# Sensor_Node.net
KiCad netlist of a schematic drawn in EAGLE
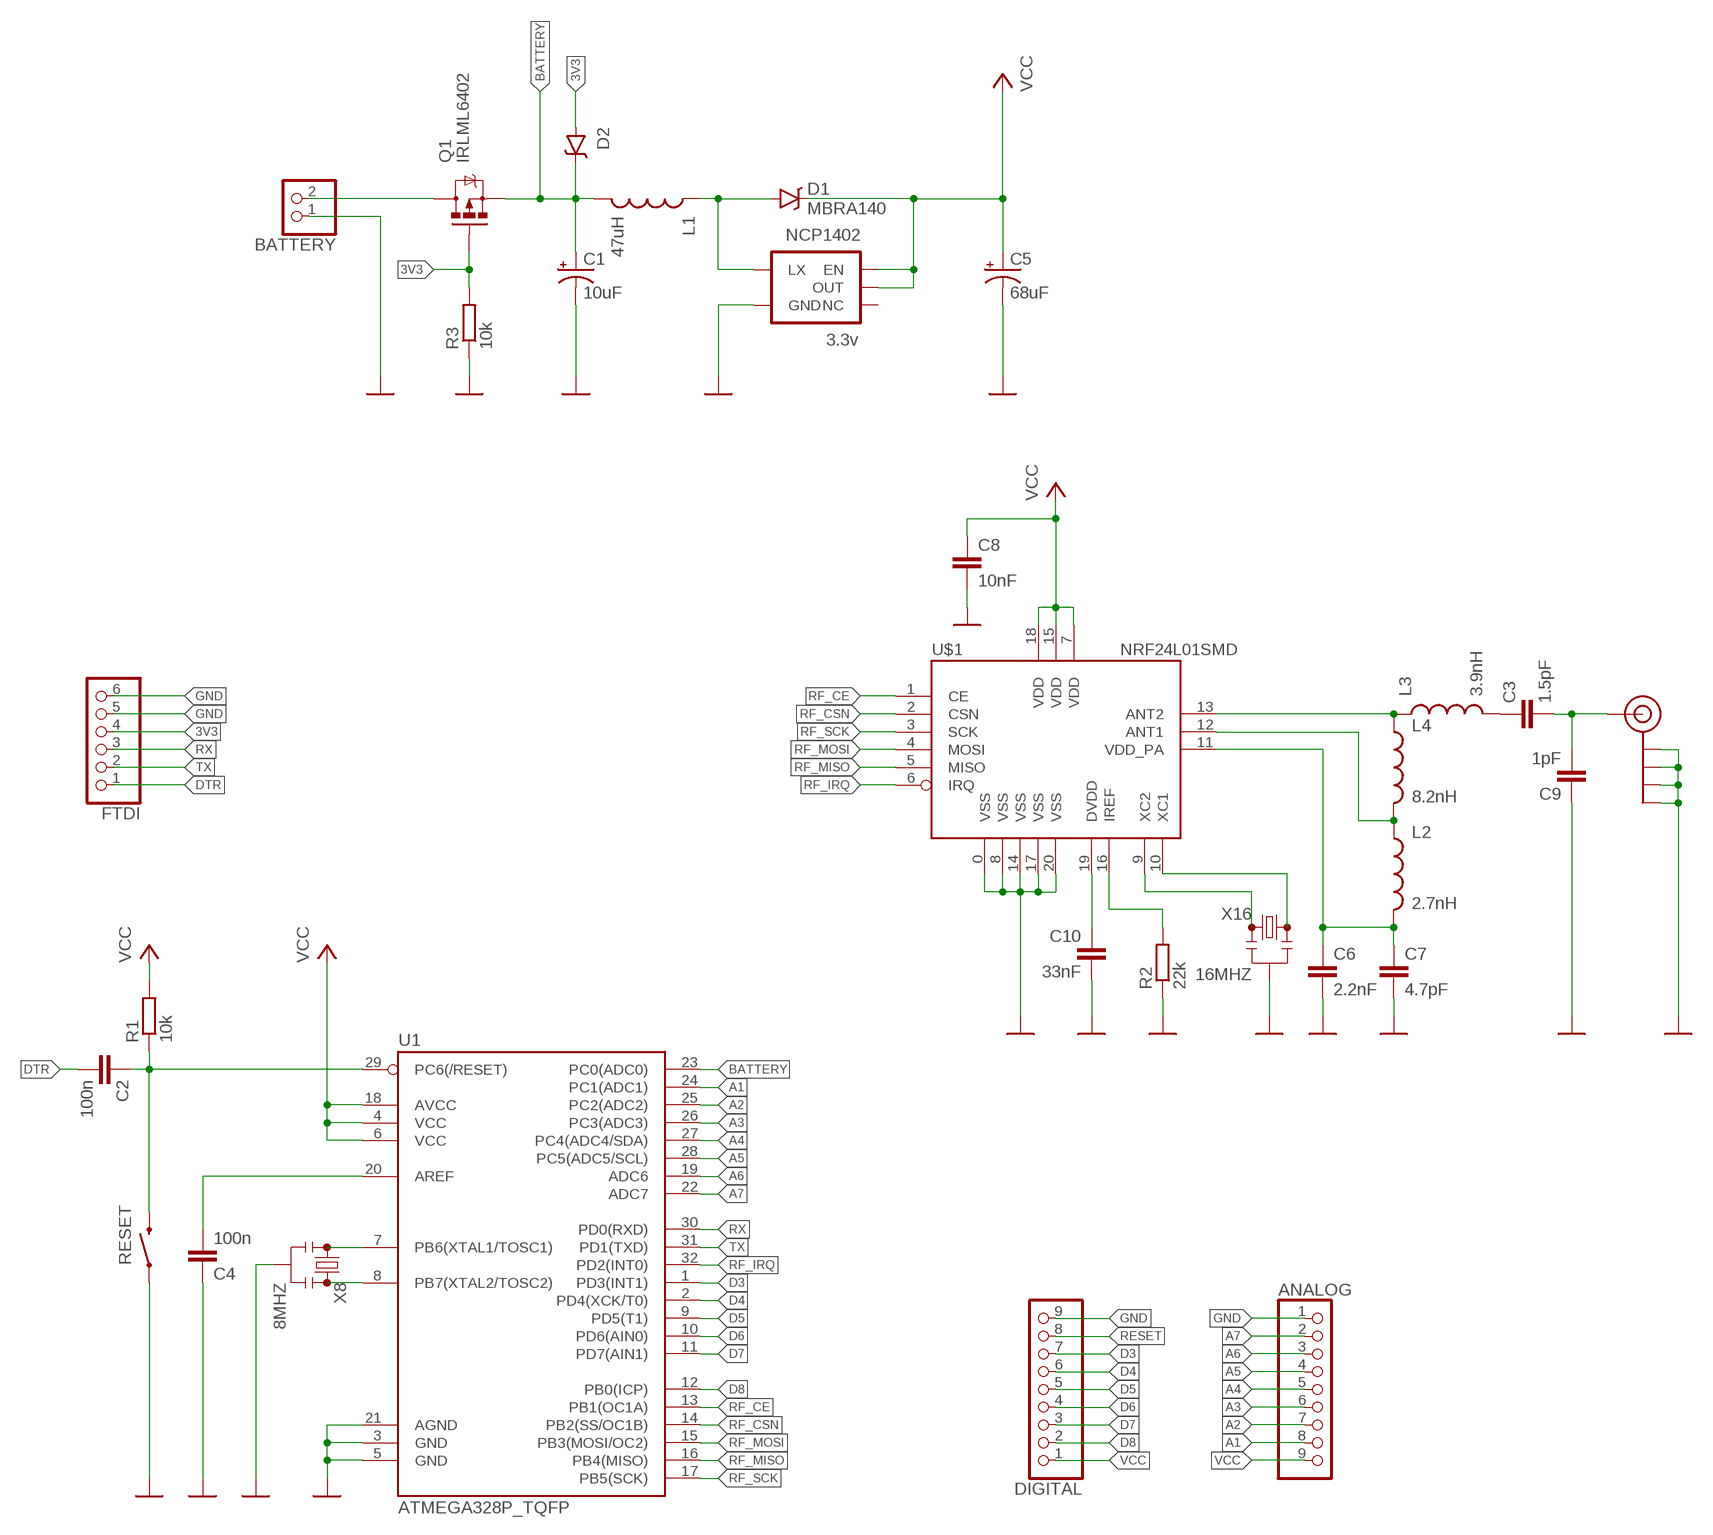
[diagram p0: schematic, sheet 1]

(export (version "E")
  (design (tool "Eeschema 10.0.6"))
  (components
    (comp (ref "ANALOG")
      (value "PINHD-1X9")
      (footprint "eagle-import:1X09")
      (libsource (lib "eagle-import") (part "PINHD-1X9"))
    )
    (comp (ref "BATTERY")
      (value "PINHD-1X2")
      (footprint "eagle-import:1X02")
      (libsource (lib "eagle-import") (part "PINHD-1X2"))
    )
    (comp (ref "C1")
      (value "10uF")
      (footprint "eagle-import:EIA3216-KIT")
      (libsource (lib "eagle-import") (part "CAP_POL1206-KIT"))
    )
    (comp (ref "C2")
      (value "100n")
      (footprint "eagle-import:C0402")
      (libsource (lib "eagle-import") (part "C-EUC0402"))
    )
    (comp (ref "C3")
      (value "1.5pF")
      (footprint "eagle-import:C0402")
      (libsource (lib "eagle-import") (part "C-EUC0402"))
    )
    (comp (ref "C4")
      (value "100n")
      (footprint "eagle-import:C0402")
      (libsource (lib "eagle-import") (part "C-EUC0402"))
    )
    (comp (ref "C5")
      (value "68uF")
      (footprint "eagle-import:EIA3528-KIT")
      (libsource (lib "eagle-import") (part "CAP_POL3528-KIT"))
    )
    (comp (ref "C6")
      (value "2.2nF")
      (footprint "eagle-import:C0402")
      (libsource (lib "eagle-import") (part "C-EUC0402"))
    )
    (comp (ref "C7")
      (value "4.7pF")
      (footprint "eagle-import:C0402")
      (libsource (lib "eagle-import") (part "C-EUC0402"))
    )
    (comp (ref "C8")
      (value "10nF")
      (footprint "eagle-import:C0402")
      (libsource (lib "eagle-import") (part "C-EUC0402"))
    )
    (comp (ref "C9")
      (value "1pF")
      (footprint "eagle-import:C0402")
      (libsource (lib "eagle-import") (part "C-EUC0402"))
    )
    (comp (ref "C10")
      (value "33nF")
      (footprint "eagle-import:C0402")
      (libsource (lib "eagle-import") (part "C-EUC0402"))
    )
    (comp (ref "D1")
      (value "MBRA140")
      (footprint "eagle-import:SMA-DIODE")
      (libsource (lib "eagle-import") (part "MBRA140"))
    )
    (comp (ref "D2")
      (value "MBRA140")
      (footprint "eagle-import:SMA-DIODE")
      (libsource (lib "eagle-import") (part "MBRA140"))
    )
    (comp (ref "DIGITAL")
      (value "PINHD-1X9")
      (footprint "eagle-import:1X09")
      (libsource (lib "eagle-import") (part "PINHD-1X9"))
    )
    (comp (ref "FTDI")
      (value "PINHD-1X6")
      (footprint "eagle-import:1X06")
      (libsource (lib "eagle-import") (part "PINHD-1X6"))
    )
    (comp (ref "J$1")
      (value "SMA_EDGE")
      (footprint "eagle-import:SMA-EDGE")
      (libsource (lib "eagle-import") (part "SMA_EDGE"))
    )
    (comp (ref "L1")
      (value "47uH")
      (footprint "eagle-import:CR54")
      (libsource (lib "eagle-import") (part "INDUCTORCR54-47UH"))
    )
    (comp (ref "L2")
      (value "2.7nH")
      (footprint "eagle-import:C0402")
      (libsource (lib "eagle-import") (part "INDUCTOR0402"))
    )
    (comp (ref "L3")
      (value "3.9nH")
      (footprint "eagle-import:C0402")
      (libsource (lib "eagle-import") (part "INDUCTOR0402"))
    )
    (comp (ref "L4")
      (value "8.2nH")
      (footprint "eagle-import:C0402")
      (libsource (lib "eagle-import") (part "INDUCTOR0402"))
    )
    (comp (ref "NCP1402")
      (value "3.3v")
      (footprint "eagle-import:SOT23-5")
      (libsource (lib "eagle-import") (part "V_REG_NCP1400_3.3V"))
    )
    (comp (ref "Q1")
      (value "IRLML6402")
      (footprint "eagle-import:SOT23-3")
      (libsource (lib "eagle-import") (part "MOSFET-PCHANNELSMD"))
    )
    (comp (ref "R1")
      (value "10k")
      (footprint "eagle-import:R0402")
      (libsource (lib "eagle-import") (part "R-EU_R0402"))
    )
    (comp (ref "R2")
      (value "22k")
      (footprint "eagle-import:R0402")
      (libsource (lib "eagle-import") (part "R-EU_R0402"))
    )
    (comp (ref "R3")
      (value "10k")
      (footprint "eagle-import:R0402")
      (libsource (lib "eagle-import") (part "R-EU_R0402"))
    )
    (comp (ref "RESET")
      (value "SWITCH-MOMENTARY-2SMD-1101NE")
      (footprint "eagle-import:TACTILE-SWITCH-1101NE")
      (libsource (lib "eagle-import") (part "SWITCH-MOMENTARY-2SMD-1101NE"))
    )
    (comp (ref "U$1")
      (value "NRF24L01SMD")
      (footprint "eagle-import:QFN20")
      (libsource (lib "eagle-import") (part "NRF24L01SMD"))
    )
    (comp (ref "U1")
      (value "ATMEGA328P_TQFP")
      (footprint "eagle-import:TQFP32-08")
      (libsource (lib "eagle-import") (part "ATMEGA328P_TQFP"))
    )
    (comp (ref "X8")
      (value "8MHZ")
      (footprint "eagle-import:RESONATOR-SMD")
      (libsource (lib "eagle-import") (part "RESONATOR8MHZ"))
    )
    (comp (ref "X16")
      (value "16MHZ")
      (footprint "eagle-import:RESONATOR-SMD")
      (libsource (lib "eagle-import") (part "RESONATOR16MHZ"))
    )
  )
  (nets
    (net (code "1") (name "3V3") (class "Default")
      (node (ref "D2") (pin "A") (pinfunction "A_A") (pintype "passive"))
      (node (ref "FTDI") (pin "4") (pinfunction "4_4") (pintype "passive"))
      (node (ref "Q1") (pin "1") (pinfunction "G_1") (pintype "passive"))
      (node (ref "R3") (pin "2") (pinfunction "2_2") (pintype "passive"))
    )
    (net (code "2") (name "A1") (class "Default")
      (node (ref "ANALOG") (pin "8") (pinfunction "8_8") (pintype "passive"))
      (node (ref "U1") (pin "24") (pinfunction "PC1(ADC1)_24") (pintype "bidirectional"))
    )
    (net (code "3") (name "A2") (class "Default")
      (node (ref "ANALOG") (pin "7") (pinfunction "7_7") (pintype "passive"))
      (node (ref "U1") (pin "25") (pinfunction "PC2(ADC2)_25") (pintype "bidirectional"))
    )
    (net (code "4") (name "A3") (class "Default")
      (node (ref "ANALOG") (pin "6") (pinfunction "6_6") (pintype "passive"))
      (node (ref "U1") (pin "26") (pinfunction "PC3(ADC3)_26") (pintype "bidirectional"))
    )
    (net (code "5") (name "A4") (class "Default")
      (node (ref "ANALOG") (pin "5") (pinfunction "5_5") (pintype "passive"))
      (node (ref "U1") (pin "27") (pinfunction "PC4(ADC4/SDA)_27") (pintype "bidirectional"))
    )
    (net (code "6") (name "A5") (class "Default")
      (node (ref "ANALOG") (pin "4") (pinfunction "4_4") (pintype "passive"))
      (node (ref "U1") (pin "28") (pinfunction "PC5(ADC5/SCL)_28") (pintype "bidirectional"))
    )
    (net (code "7") (name "A6") (class "Default")
      (node (ref "ANALOG") (pin "3") (pinfunction "3_3") (pintype "passive"))
      (node (ref "U1") (pin "19") (pinfunction "ADC6_19") (pintype "bidirectional"))
    )
    (net (code "8") (name "A7") (class "Default")
      (node (ref "ANALOG") (pin "2") (pinfunction "2_2") (pintype "passive"))
      (node (ref "U1") (pin "22") (pinfunction "ADC7_22") (pintype "bidirectional"))
    )
    (net (code "9") (name "BATTERY") (class "Default")
      (node (ref "C1") (pin "A") (pinfunction "+_A") (pintype "passive"))
      (node (ref "D2") (pin "C") (pinfunction "C_C") (pintype "passive"))
      (node (ref "L1") (pin "P$2") (pinfunction "2_P$2") (pintype "passive"))
      (node (ref "Q1") (pin "2") (pinfunction "S_2") (pintype "passive"))
      (node (ref "U1") (pin "23") (pinfunction "PC0(ADC0)_23") (pintype "bidirectional"))
    )
    (net (code "10") (name "D3") (class "Default")
      (node (ref "DIGITAL") (pin "7") (pinfunction "7_7") (pintype "passive"))
      (node (ref "U1") (pin "1") (pinfunction "PD3(INT1)_1") (pintype "bidirectional"))
    )
    (net (code "11") (name "D4") (class "Default")
      (node (ref "DIGITAL") (pin "6") (pinfunction "6_6") (pintype "passive"))
      (node (ref "U1") (pin "2") (pinfunction "PD4(XCK/T0)_2") (pintype "bidirectional"))
    )
    (net (code "12") (name "D5") (class "Default")
      (node (ref "DIGITAL") (pin "5") (pinfunction "5_5") (pintype "passive"))
      (node (ref "U1") (pin "9") (pinfunction "PD5(T1)_9") (pintype "bidirectional"))
    )
    (net (code "13") (name "D6") (class "Default")
      (node (ref "DIGITAL") (pin "4") (pinfunction "4_4") (pintype "passive"))
      (node (ref "U1") (pin "10") (pinfunction "PD6(AIN0)_10") (pintype "bidirectional"))
    )
    (net (code "14") (name "D7") (class "Default")
      (node (ref "DIGITAL") (pin "3") (pinfunction "3_3") (pintype "passive"))
      (node (ref "U1") (pin "11") (pinfunction "PD7(AIN1)_11") (pintype "bidirectional"))
    )
    (net (code "15") (name "D8") (class "Default")
      (node (ref "DIGITAL") (pin "2") (pinfunction "2_2") (pintype "passive"))
      (node (ref "U1") (pin "12") (pinfunction "PB0(ICP)_12") (pintype "bidirectional"))
    )
    (net (code "16") (name "DTR") (class "Default")
      (node (ref "C2") (pin "2") (pinfunction "2_2") (pintype "passive"))
      (node (ref "FTDI") (pin "1") (pinfunction "1_1") (pintype "passive"))
    )
    (net (code "17") (name "GND") (class "Default")
      (node (ref "ANALOG") (pin "1") (pinfunction "1_1") (pintype "passive"))
      (node (ref "BATTERY") (pin "1") (pinfunction "1_1") (pintype "passive"))
      (node (ref "C1") (pin "C") (pinfunction "-_C") (pintype "passive"))
      (node (ref "C10") (pin "2") (pinfunction "2_2") (pintype "passive"))
      (node (ref "C4") (pin "1") (pinfunction "1_1") (pintype "passive"))
      (node (ref "C5") (pin "C") (pinfunction "-_C") (pintype "passive"))
      (node (ref "C6") (pin "2") (pinfunction "2_2") (pintype "passive"))
      (node (ref "C7") (pin "2") (pinfunction "2_2") (pintype "passive"))
      (node (ref "C8") (pin "2") (pinfunction "2_2") (pintype "passive"))
      (node (ref "C9") (pin "1") (pinfunction "1_1") (pintype "passive"))
      (node (ref "DIGITAL") (pin "9") (pinfunction "9_9") (pintype "passive"))
      (node (ref "FTDI") (pin "5") (pinfunction "5_5") (pintype "passive"))
      (node (ref "FTDI") (pin "6") (pinfunction "6_6") (pintype "passive"))
      (node (ref "J$1") (pin "GND@0") (pinfunction "GND_GND@0") (pintype "bidirectional"))
      (node (ref "J$1") (pin "GND@1") (pinfunction "GND_GND@1") (pintype "bidirectional"))
      (node (ref "J$1") (pin "GND@2") (pinfunction "GND_GND@2") (pintype "bidirectional"))
      (node (ref "J$1") (pin "GND@3") (pinfunction "GND_GND@3") (pintype "bidirectional"))
      (node (ref "NCP1402") (pin "4") (pinfunction "GND_4") (pintype "input"))
      (node (ref "R2") (pin "1") (pinfunction "1_1") (pintype "passive"))
      (node (ref "R3") (pin "1") (pinfunction "1_1") (pintype "passive"))
      (node (ref "RESET") (pin "1") (pinfunction "1_1") (pintype "passive"))
      (node (ref "U$1") (pin "0") (pinfunction "VSS_0") (pintype "power_in"))
      (node (ref "U$1") (pin "14") (pinfunction "VSS_14") (pintype "power_in"))
      (node (ref "U$1") (pin "17") (pinfunction "VSS_17") (pintype "power_in"))
      (node (ref "U$1") (pin "20") (pinfunction "VSS_20") (pintype "power_in"))
      (node (ref "U$1") (pin "8") (pinfunction "VSS_8") (pintype "power_in"))
      (node (ref "U1") (pin "21") (pinfunction "AGND_21") (pintype "bidirectional"))
      (node (ref "U1") (pin "3") (pinfunction "GND_3") (pintype "bidirectional"))
      (node (ref "U1") (pin "5") (pinfunction "GND_5") (pintype "bidirectional"))
      (node (ref "X16") (pin "2") (pinfunction "2_2") (pintype "passive"))
      (node (ref "X8") (pin "2") (pinfunction "2_2") (pintype "passive"))
    )
    (net (code "18") (name "Net-(C3-Pad1)") (class "Default")
      (node (ref "C3") (pin "1") (pinfunction "1_1") (pintype "passive"))
      (node (ref "L3") (pin "2") (pinfunction "2_2") (pintype "passive"))
    )
    (net (code "19") (name "Net-(J$1-SIGNAL)") (class "Default")
      (node (ref "C3") (pin "2") (pinfunction "2_2") (pintype "passive"))
      (node (ref "C9") (pin "2") (pinfunction "2_2") (pintype "passive"))
      (node (ref "J$1") (pin "SIG") (pinfunction "SIGNAL_SIG") (pintype "bidirectional"))
    )
    (net (code "20") (name "Net-(L1-1)") (class "Default")
      (node (ref "D1") (pin "A") (pinfunction "A_A") (pintype "passive"))
      (node (ref "L1") (pin "P$1") (pinfunction "1_P$1") (pintype "passive"))
      (node (ref "NCP1402") (pin "5") (pinfunction "LX_5") (pintype "input"))
    )
    (net (code "21") (name "Net-(Q1-D)") (class "Default")
      (node (ref "BATTERY") (pin "2") (pinfunction "2_2") (pintype "passive"))
      (node (ref "Q1") (pin "3") (pinfunction "D_3") (pintype "passive"))
    )
    (net (code "22") (name "Net-(U$1-ANT1)") (class "Default")
      (node (ref "L2") (pin "1") (pinfunction "1_1") (pintype "passive"))
      (node (ref "L4") (pin "2") (pinfunction "2_2") (pintype "passive"))
      (node (ref "U$1") (pin "12") (pinfunction "ANT1_12") (pintype "output"))
    )
    (net (code "23") (name "Net-(U$1-ANT2)") (class "Default")
      (node (ref "L3") (pin "1") (pinfunction "1_1") (pintype "passive"))
      (node (ref "L4") (pin "1") (pinfunction "1_1") (pintype "passive"))
      (node (ref "U$1") (pin "13") (pinfunction "ANT2_13") (pintype "output"))
    )
    (net (code "24") (name "Net-(U$1-DVDD)") (class "Default")
      (node (ref "C10") (pin "1") (pinfunction "1_1") (pintype "passive"))
      (node (ref "U$1") (pin "19") (pinfunction "DVDD_19") (pintype "power_in"))
    )
    (net (code "25") (name "Net-(U$1-IREF)") (class "Default")
      (node (ref "R2") (pin "2") (pinfunction "2_2") (pintype "passive"))
      (node (ref "U$1") (pin "16") (pinfunction "IREF_16") (pintype "input"))
    )
    (net (code "26") (name "Net-(U$1-VDD_PA)") (class "Default")
      (node (ref "C6") (pin "1") (pinfunction "1_1") (pintype "passive"))
      (node (ref "C7") (pin "1") (pinfunction "1_1") (pintype "passive"))
      (node (ref "L2") (pin "2") (pinfunction "2_2") (pintype "passive"))
      (node (ref "U$1") (pin "11") (pinfunction "VDD_PA_11") (pintype "power_in"))
    )
    (net (code "27") (name "Net-(U$1-XC1)") (class "Default")
      (node (ref "U$1") (pin "10") (pinfunction "XC1_10") (pintype "input"))
      (node (ref "X16") (pin "1") (pinfunction "1_1") (pintype "passive"))
    )
    (net (code "28") (name "Net-(U$1-XC2)") (class "Default")
      (node (ref "U$1") (pin "9") (pinfunction "XC2_9") (pintype "input"))
      (node (ref "X16") (pin "3") (pinfunction "3_3") (pintype "passive"))
    )
    (net (code "29") (name "Net-(U1-AREF)") (class "Default")
      (node (ref "C4") (pin "2") (pinfunction "2_2") (pintype "passive"))
      (node (ref "U1") (pin "20") (pinfunction "AREF_20") (pintype "bidirectional"))
    )
    (net (code "30") (name "Net-(U1-PB6(XTAL1{slash}TOSC1))") (class "Default")
      (node (ref "U1") (pin "7") (pinfunction "PB6(XTAL1/TOSC1)_7") (pintype "bidirectional"))
      (node (ref "X8") (pin "1") (pinfunction "1_1") (pintype "passive"))
    )
    (net (code "31") (name "Net-(U1-PB7(XTAL2{slash}TOSC2))") (class "Default")
      (node (ref "U1") (pin "8") (pinfunction "PB7(XTAL2/TOSC2)_8") (pintype "bidirectional"))
      (node (ref "X8") (pin "3") (pinfunction "3_3") (pintype "passive"))
    )
    (net (code "32") (name "RESET") (class "Default")
      (node (ref "C2") (pin "1") (pinfunction "1_1") (pintype "passive"))
      (node (ref "DIGITAL") (pin "8") (pinfunction "8_8") (pintype "passive"))
      (node (ref "R1") (pin "1") (pinfunction "1_1") (pintype "passive"))
      (node (ref "RESET") (pin "2") (pinfunction "2_2") (pintype "passive"))
      (node (ref "U1") (pin "29") (pinfunction "PC6(/RESET)_29") (pintype "bidirectional"))
    )
    (net (code "33") (name "RF_CE") (class "Default")
      (node (ref "U$1") (pin "1") (pinfunction "CE_1") (pintype "input"))
      (node (ref "U1") (pin "13") (pinfunction "PB1(OC1A)_13") (pintype "bidirectional"))
    )
    (net (code "34") (name "RF_CSN") (class "Default")
      (node (ref "U$1") (pin "2") (pinfunction "CSN_2") (pintype "input"))
      (node (ref "U1") (pin "14") (pinfunction "PB2(SS/OC1B)_14") (pintype "bidirectional"))
    )
    (net (code "35") (name "RF_IRQ") (class "Default")
      (node (ref "U$1") (pin "6") (pinfunction "IRQ_6") (pintype "output"))
      (node (ref "U1") (pin "32") (pinfunction "PD2(INT0)_32") (pintype "bidirectional"))
    )
    (net (code "36") (name "RF_MISO") (class "Default")
      (node (ref "U$1") (pin "5") (pinfunction "MISO_5") (pintype "output"))
      (node (ref "U1") (pin "16") (pinfunction "PB4(MISO)_16") (pintype "bidirectional"))
    )
    (net (code "37") (name "RF_MOSI") (class "Default")
      (node (ref "U$1") (pin "4") (pinfunction "MOSI_4") (pintype "input"))
      (node (ref "U1") (pin "15") (pinfunction "PB3(MOSI/OC2)_15") (pintype "bidirectional"))
    )
    (net (code "38") (name "RF_SCK") (class "Default")
      (node (ref "U$1") (pin "3") (pinfunction "SCK_3") (pintype "input"))
      (node (ref "U1") (pin "17") (pinfunction "PB5(SCK)_17") (pintype "bidirectional"))
    )
    (net (code "39") (name "RX") (class "Default")
      (node (ref "FTDI") (pin "3") (pinfunction "3_3") (pintype "passive"))
      (node (ref "U1") (pin "30") (pinfunction "PD0(RXD)_30") (pintype "bidirectional"))
    )
    (net (code "40") (name "TX") (class "Default")
      (node (ref "FTDI") (pin "2") (pinfunction "2_2") (pintype "passive"))
      (node (ref "U1") (pin "31") (pinfunction "PD1(TXD)_31") (pintype "bidirectional"))
    )
    (net (code "41") (name "VCC") (class "Default")
      (node (ref "ANALOG") (pin "9") (pinfunction "9_9") (pintype "passive"))
      (node (ref "C5") (pin "A") (pinfunction "+_A") (pintype "passive"))
      (node (ref "C8") (pin "1") (pinfunction "1_1") (pintype "passive"))
      (node (ref "D1") (pin "C") (pinfunction "C_C") (pintype "passive"))
      (node (ref "DIGITAL") (pin "1") (pinfunction "1_1") (pintype "passive"))
      (node (ref "NCP1402") (pin "1") (pinfunction "EN_1") (pintype "input"))
      (node (ref "NCP1402") (pin "2") (pinfunction "OUT_2") (pintype "passive"))
      (node (ref "R1") (pin "2") (pinfunction "2_2") (pintype "passive"))
      (node (ref "U$1") (pin "15") (pinfunction "VDD_15") (pintype "power_in"))
      (node (ref "U$1") (pin "18") (pinfunction "VDD_18") (pintype "power_in"))
      (node (ref "U$1") (pin "7") (pinfunction "VDD_7") (pintype "power_in"))
      (node (ref "U1") (pin "18") (pinfunction "AVCC_18") (pintype "bidirectional"))
      (node (ref "U1") (pin "4") (pinfunction "VCC_4") (pintype "bidirectional"))
      (node (ref "U1") (pin "6") (pinfunction "VCC_6") (pintype "bidirectional"))
    )
    (net (code "42") (name "unconnected-(NCP1402-NC-Pad3)") (class "Default")
      (node (ref "NCP1402") (pin "3") (pinfunction "NC_3") (pintype "input"))
    )
  )
)
